# BatteryMonitor.net
KiCad netlist of a schematic drawn in Altium Designer
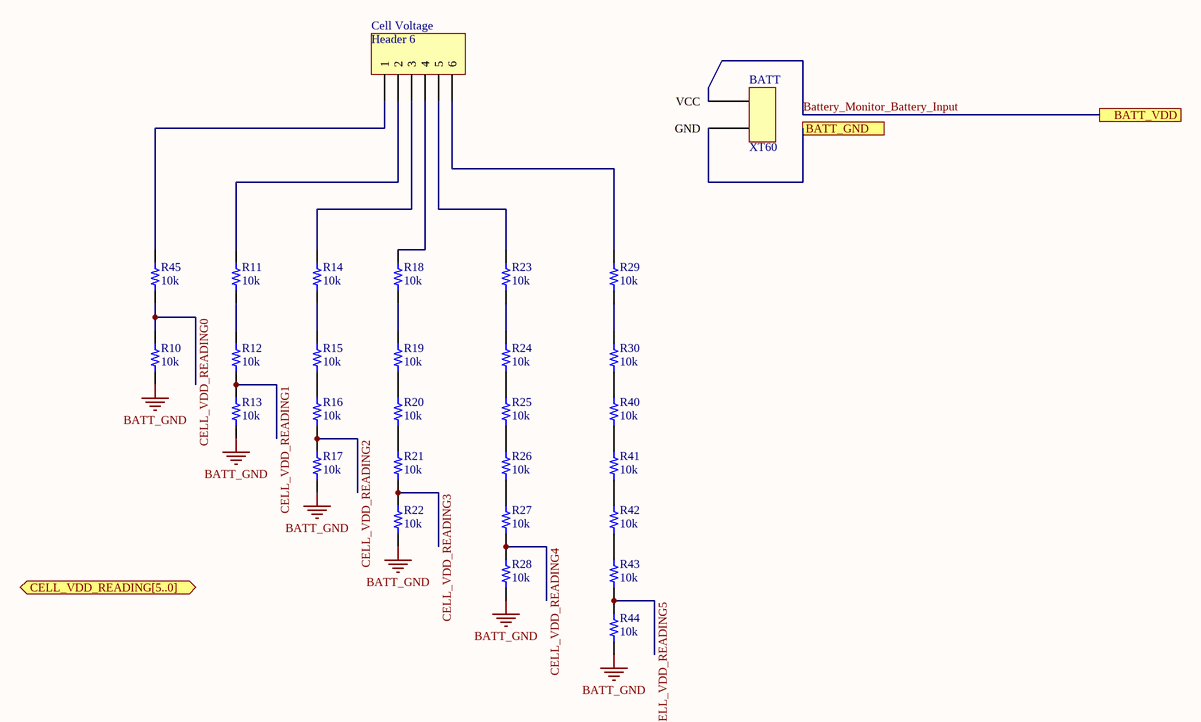
[diagram p0: BatteryMonitor.SchDoc]

(export (version "E")
  (design (tool "Eeschema 10.0.6"))
  (components
    (comp (ref "BATT") (value "XT60") (footprint "PcbLib2:XT60") (libsource (lib "Schlib2") (part "XT60")))
    (comp (ref "Cell Voltage")
      (value "Header 6")
      (footprint "HDR1X6")
      (description "Header, 6-Pin")
      (fields (field (name "PUBLISHER") "Altium Limited"))
      (libsource (lib "Miscellaneous Connectors") (part "Header 6"))
    )
    (comp (ref "R10")
      (value "10k")
      (footprint "RES 0402/1005")
      (description "RES SMD 10K OHM 1% 1/10W 0402")
      (fields
        (field (name "PART NUMBER") "ERJ-2RKF1002X")
        (field (name "MANUFACTURER") "Panasonic Electronic Components")
      )
      (libsource (lib "Celestial Library Database") (part "Resistor"))
    )
    (comp (ref "R11")
      (value "10k")
      (footprint "RES 0402/1005")
      (description "RES SMD 10K OHM 1% 1/10W 0402")
      (fields
        (field (name "PART NUMBER") "ERJ-2RKF1002X")
        (field (name "MANUFACTURER") "Panasonic Electronic Components")
      )
      (libsource (lib "Celestial Library Database") (part "Resistor"))
    )
    (comp (ref "R12")
      (value "10k")
      (footprint "RES 0402/1005")
      (description "RES SMD 10K OHM 1% 1/10W 0402")
      (fields
        (field (name "PART NUMBER") "ERJ-2RKF1002X")
        (field (name "MANUFACTURER") "Panasonic Electronic Components")
      )
      (libsource (lib "Celestial Library Database") (part "Resistor"))
    )
    (comp (ref "R13")
      (value "10k")
      (footprint "RES 0402/1005")
      (description "RES SMD 10K OHM 1% 1/10W 0402")
      (fields
        (field (name "PART NUMBER") "ERJ-2RKF1002X")
        (field (name "MANUFACTURER") "Panasonic Electronic Components")
      )
      (libsource (lib "Celestial Library Database") (part "Resistor"))
    )
    (comp (ref "R14")
      (value "10k")
      (footprint "RES 0402/1005")
      (description "RES SMD 10K OHM 1% 1/10W 0402")
      (fields
        (field (name "PART NUMBER") "ERJ-2RKF1002X")
        (field (name "MANUFACTURER") "Panasonic Electronic Components")
      )
      (libsource (lib "Celestial Library Database") (part "Resistor"))
    )
    (comp (ref "R15")
      (value "10k")
      (footprint "RES 0402/1005")
      (description "RES SMD 10K OHM 1% 1/10W 0402")
      (fields
        (field (name "PART NUMBER") "ERJ-2RKF1002X")
        (field (name "MANUFACTURER") "Panasonic Electronic Components")
      )
      (libsource (lib "Celestial Library Database") (part "Resistor"))
    )
    (comp (ref "R16")
      (value "10k")
      (footprint "RES 0402/1005")
      (description "RES SMD 10K OHM 1% 1/10W 0402")
      (fields
        (field (name "PART NUMBER") "ERJ-2RKF1002X")
        (field (name "MANUFACTURER") "Panasonic Electronic Components")
      )
      (libsource (lib "Celestial Library Database") (part "Resistor"))
    )
    (comp (ref "R17")
      (value "10k")
      (footprint "RES 0402/1005")
      (description "RES SMD 10K OHM 1% 1/10W 0402")
      (fields
        (field (name "PART NUMBER") "ERJ-2RKF1002X")
        (field (name "MANUFACTURER") "Panasonic Electronic Components")
      )
      (libsource (lib "Celestial Library Database") (part "Resistor"))
    )
    (comp (ref "R18")
      (value "10k")
      (footprint "RES 0402/1005")
      (description "RES SMD 10K OHM 1% 1/10W 0402")
      (fields
        (field (name "PART NUMBER") "ERJ-2RKF1002X")
        (field (name "MANUFACTURER") "Panasonic Electronic Components")
      )
      (libsource (lib "Celestial Library Database") (part "Resistor"))
    )
    (comp (ref "R19")
      (value "10k")
      (footprint "RES 0402/1005")
      (description "RES SMD 10K OHM 1% 1/10W 0402")
      (fields
        (field (name "PART NUMBER") "ERJ-2RKF1002X")
        (field (name "MANUFACTURER") "Panasonic Electronic Components")
      )
      (libsource (lib "Celestial Library Database") (part "Resistor"))
    )
    (comp (ref "R20")
      (value "10k")
      (footprint "RES 0402/1005")
      (description "RES SMD 10K OHM 1% 1/10W 0402")
      (fields
        (field (name "PART NUMBER") "ERJ-2RKF1002X")
        (field (name "MANUFACTURER") "Panasonic Electronic Components")
      )
      (libsource (lib "Celestial Library Database") (part "Resistor"))
    )
    (comp (ref "R21")
      (value "10k")
      (footprint "RES 0402/1005")
      (description "RES SMD 10K OHM 1% 1/10W 0402")
      (fields
        (field (name "PART NUMBER") "ERJ-2RKF1002X")
        (field (name "MANUFACTURER") "Panasonic Electronic Components")
      )
      (libsource (lib "Celestial Library Database") (part "Resistor"))
    )
    (comp (ref "R22")
      (value "10k")
      (footprint "RES 0402/1005")
      (description "RES SMD 10K OHM 1% 1/10W 0402")
      (fields
        (field (name "PART NUMBER") "ERJ-2RKF1002X")
        (field (name "MANUFACTURER") "Panasonic Electronic Components")
      )
      (libsource (lib "Celestial Library Database") (part "Resistor"))
    )
    (comp (ref "R23")
      (value "10k")
      (footprint "RES 0402/1005")
      (description "RES SMD 10K OHM 1% 1/10W 0402")
      (fields
        (field (name "PART NUMBER") "ERJ-2RKF1002X")
        (field (name "MANUFACTURER") "Panasonic Electronic Components")
      )
      (libsource (lib "Celestial Library Database") (part "Resistor"))
    )
    (comp (ref "R24")
      (value "10k")
      (footprint "RES 0402/1005")
      (description "RES SMD 10K OHM 1% 1/10W 0402")
      (fields
        (field (name "PART NUMBER") "ERJ-2RKF1002X")
        (field (name "MANUFACTURER") "Panasonic Electronic Components")
      )
      (libsource (lib "Celestial Library Database") (part "Resistor"))
    )
    (comp (ref "R25")
      (value "10k")
      (footprint "RES 0402/1005")
      (description "RES SMD 10K OHM 1% 1/10W 0402")
      (fields
        (field (name "PART NUMBER") "ERJ-2RKF1002X")
        (field (name "MANUFACTURER") "Panasonic Electronic Components")
      )
      (libsource (lib "Celestial Library Database") (part "Resistor"))
    )
    (comp (ref "R26")
      (value "10k")
      (footprint "RES 0402/1005")
      (description "RES SMD 10K OHM 1% 1/10W 0402")
      (fields
        (field (name "PART NUMBER") "ERJ-2RKF1002X")
        (field (name "MANUFACTURER") "Panasonic Electronic Components")
      )
      (libsource (lib "Celestial Library Database") (part "Resistor"))
    )
    (comp (ref "R27")
      (value "10k")
      (footprint "RES 0402/1005")
      (description "RES SMD 10K OHM 1% 1/10W 0402")
      (fields
        (field (name "PART NUMBER") "ERJ-2RKF1002X")
        (field (name "MANUFACTURER") "Panasonic Electronic Components")
      )
      (libsource (lib "Celestial Library Database") (part "Resistor"))
    )
    (comp (ref "R28")
      (value "10k")
      (footprint "RES 0402/1005")
      (description "RES SMD 10K OHM 1% 1/10W 0402")
      (fields
        (field (name "PART NUMBER") "ERJ-2RKF1002X")
        (field (name "MANUFACTURER") "Panasonic Electronic Components")
      )
      (libsource (lib "Celestial Library Database") (part "Resistor"))
    )
    (comp (ref "R29")
      (value "10k")
      (footprint "RES 0402/1005")
      (description "RES SMD 10K OHM 1% 1/10W 0402")
      (fields
        (field (name "PART NUMBER") "ERJ-2RKF1002X")
        (field (name "MANUFACTURER") "Panasonic Electronic Components")
      )
      (libsource (lib "Celestial Library Database") (part "Resistor"))
    )
    (comp (ref "R30")
      (value "10k")
      (footprint "RES 0402/1005")
      (description "RES SMD 10K OHM 1% 1/10W 0402")
      (fields
        (field (name "PART NUMBER") "ERJ-2RKF1002X")
        (field (name "MANUFACTURER") "Panasonic Electronic Components")
      )
      (libsource (lib "Celestial Library Database") (part "Resistor"))
    )
    (comp (ref "R40")
      (value "10k")
      (footprint "RES 0402/1005")
      (description "RES SMD 10K OHM 1% 1/10W 0402")
      (fields
        (field (name "PART NUMBER") "ERJ-2RKF1002X")
        (field (name "MANUFACTURER") "Panasonic Electronic Components")
      )
      (libsource (lib "Celestial Library Database") (part "Resistor"))
    )
    (comp (ref "R41")
      (value "10k")
      (footprint "RES 0402/1005")
      (description "RES SMD 10K OHM 1% 1/10W 0402")
      (fields
        (field (name "PART NUMBER") "ERJ-2RKF1002X")
        (field (name "MANUFACTURER") "Panasonic Electronic Components")
      )
      (libsource (lib "Celestial Library Database") (part "Resistor"))
    )
    (comp (ref "R42")
      (value "10k")
      (footprint "RES 0402/1005")
      (description "RES SMD 10K OHM 1% 1/10W 0402")
      (fields
        (field (name "PART NUMBER") "ERJ-2RKF1002X")
        (field (name "MANUFACTURER") "Panasonic Electronic Components")
      )
      (libsource (lib "Celestial Library Database") (part "Resistor"))
    )
    (comp (ref "R43")
      (value "10k")
      (footprint "RES 0402/1005")
      (description "RES SMD 10K OHM 1% 1/10W 0402")
      (fields
        (field (name "PART NUMBER") "ERJ-2RKF1002X")
        (field (name "MANUFACTURER") "Panasonic Electronic Components")
      )
      (libsource (lib "Celestial Library Database") (part "Resistor"))
    )
    (comp (ref "R44")
      (value "10k")
      (footprint "RES 0402/1005")
      (description "RES SMD 10K OHM 1% 1/10W 0402")
      (fields
        (field (name "PART NUMBER") "ERJ-2RKF1002X")
        (field (name "MANUFACTURER") "Panasonic Electronic Components")
      )
      (libsource (lib "Celestial Library Database") (part "Resistor"))
    )
    (comp (ref "R45")
      (value "10k")
      (footprint "RES 0402/1005")
      (description "RES SMD 10K OHM 1% 1/10W 0402")
      (fields
        (field (name "PART NUMBER") "ERJ-2RKF1002X")
        (field (name "MANUFACTURER") "Panasonic Electronic Components")
      )
      (libsource (lib "Celestial Library Database") (part "Resistor"))
    )
  )
  (nets
    (net (code "2") (name "/CELL_VDD_READING0") (class "Default")
      (node (ref "R10") (pin "2") (pinfunction "2_2") (pintype "passive"))
      (node (ref "R45") (pin "1") (pinfunction "1_1") (pintype "passive"))
    )
    (net (code "3") (name "/CELL_VDD_READING1") (class "Default")
      (node (ref "R12") (pin "1") (pinfunction "1_1") (pintype "passive"))
      (node (ref "R13") (pin "2") (pinfunction "2_2") (pintype "passive"))
    )
    (net (code "4") (name "/CELL_VDD_READING2") (class "Default")
      (node (ref "R16") (pin "1") (pinfunction "1_1") (pintype "passive"))
      (node (ref "R17") (pin "2") (pinfunction "2_2") (pintype "passive"))
    )
    (net (code "5") (name "/CELL_VDD_READING3") (class "Default")
      (node (ref "R21") (pin "1") (pinfunction "1_1") (pintype "passive"))
      (node (ref "R22") (pin "2") (pinfunction "2_2") (pintype "passive"))
    )
    (net (code "6") (name "/CELL_VDD_READING4") (class "Default")
      (node (ref "R27") (pin "1") (pinfunction "1_1") (pintype "passive"))
      (node (ref "R28") (pin "2") (pinfunction "2_2") (pintype "passive"))
    )
    (net (code "7") (name "/CELL_VDD_READING5") (class "Default")
      (node (ref "R43") (pin "1") (pinfunction "1_1") (pintype "passive"))
      (node (ref "R44") (pin "2") (pinfunction "2_2") (pintype "passive"))
    )
    (net (code "9") (name "BATT_GND") (class "Default")
      (node (ref "R10") (pin "1") (pinfunction "1_1") (pintype "passive"))
      (node (ref "R13") (pin "1") (pinfunction "1_1") (pintype "passive"))
      (node (ref "R17") (pin "1") (pinfunction "1_1") (pintype "passive"))
      (node (ref "R22") (pin "1") (pinfunction "1_1") (pintype "passive"))
      (node (ref "R28") (pin "1") (pinfunction "1_1") (pintype "passive"))
      (node (ref "R44") (pin "1") (pinfunction "1_1") (pintype "passive"))
    )
    (net (code "10") (name "Net-(Cell Voltage-Pad1)") (class "Default")
      (node (ref "Cell Voltage") (pin "1") (pinfunction "1_1") (pintype "passive"))
      (node (ref "R45") (pin "2") (pinfunction "2_2") (pintype "passive"))
    )
    (net (code "11") (name "Net-(Cell Voltage-Pad2)") (class "Default")
      (node (ref "Cell Voltage") (pin "2") (pinfunction "2_2") (pintype "passive"))
      (node (ref "R11") (pin "2") (pinfunction "2_2") (pintype "passive"))
    )
    (net (code "12") (name "Net-(Cell Voltage-Pad3)") (class "Default")
      (node (ref "Cell Voltage") (pin "3") (pinfunction "3_3") (pintype "passive"))
      (node (ref "R14") (pin "2") (pinfunction "2_2") (pintype "passive"))
    )
    (net (code "13") (name "Net-(Cell Voltage-Pad4)") (class "Default")
      (node (ref "Cell Voltage") (pin "4") (pinfunction "4_4") (pintype "passive"))
      (node (ref "R18") (pin "2") (pinfunction "2_2") (pintype "passive"))
    )
    (net (code "14") (name "Net-(Cell Voltage-Pad5)") (class "Default")
      (node (ref "Cell Voltage") (pin "5") (pinfunction "5_5") (pintype "passive"))
      (node (ref "R23") (pin "2") (pinfunction "2_2") (pintype "passive"))
    )
    (net (code "15") (name "Net-(Cell Voltage-Pad6)") (class "Default")
      (node (ref "Cell Voltage") (pin "6") (pinfunction "6_6") (pintype "passive"))
      (node (ref "R29") (pin "2") (pinfunction "2_2") (pintype "passive"))
    )
    (net (code "16") (name "Net-(R11-Pad1)") (class "Default")
      (node (ref "R11") (pin "1") (pinfunction "1_1") (pintype "passive"))
      (node (ref "R12") (pin "2") (pinfunction "2_2") (pintype "passive"))
    )
    (net (code "17") (name "Net-(R14-Pad1)") (class "Default")
      (node (ref "R14") (pin "1") (pinfunction "1_1") (pintype "passive"))
      (node (ref "R15") (pin "2") (pinfunction "2_2") (pintype "passive"))
    )
    (net (code "18") (name "Net-(R15-Pad1)") (class "Default")
      (node (ref "R15") (pin "1") (pinfunction "1_1") (pintype "passive"))
      (node (ref "R16") (pin "2") (pinfunction "2_2") (pintype "passive"))
    )
    (net (code "19") (name "Net-(R18-Pad1)") (class "Default")
      (node (ref "R18") (pin "1") (pinfunction "1_1") (pintype "passive"))
      (node (ref "R19") (pin "2") (pinfunction "2_2") (pintype "passive"))
    )
    (net (code "20") (name "Net-(R19-Pad1)") (class "Default")
      (node (ref "R19") (pin "1") (pinfunction "1_1") (pintype "passive"))
      (node (ref "R20") (pin "2") (pinfunction "2_2") (pintype "passive"))
    )
    (net (code "21") (name "Net-(R20-Pad1)") (class "Default")
      (node (ref "R20") (pin "1") (pinfunction "1_1") (pintype "passive"))
      (node (ref "R21") (pin "2") (pinfunction "2_2") (pintype "passive"))
    )
    (net (code "22") (name "Net-(R23-Pad1)") (class "Default")
      (node (ref "R23") (pin "1") (pinfunction "1_1") (pintype "passive"))
      (node (ref "R24") (pin "2") (pinfunction "2_2") (pintype "passive"))
    )
    (net (code "23") (name "Net-(R24-Pad1)") (class "Default")
      (node (ref "R24") (pin "1") (pinfunction "1_1") (pintype "passive"))
      (node (ref "R25") (pin "2") (pinfunction "2_2") (pintype "passive"))
    )
    (net (code "24") (name "Net-(R25-Pad1)") (class "Default")
      (node (ref "R25") (pin "1") (pinfunction "1_1") (pintype "passive"))
      (node (ref "R26") (pin "2") (pinfunction "2_2") (pintype "passive"))
    )
    (net (code "25") (name "Net-(R26-Pad1)") (class "Default")
      (node (ref "R26") (pin "1") (pinfunction "1_1") (pintype "passive"))
      (node (ref "R27") (pin "2") (pinfunction "2_2") (pintype "passive"))
    )
    (net (code "26") (name "Net-(R29-Pad1)") (class "Default")
      (node (ref "R29") (pin "1") (pinfunction "1_1") (pintype "passive"))
      (node (ref "R30") (pin "2") (pinfunction "2_2") (pintype "passive"))
    )
    (net (code "27") (name "Net-(R30-Pad1)") (class "Default")
      (node (ref "R30") (pin "1") (pinfunction "1_1") (pintype "passive"))
      (node (ref "R40") (pin "2") (pinfunction "2_2") (pintype "passive"))
    )
    (net (code "28") (name "Net-(R40-Pad1)") (class "Default")
      (node (ref "R40") (pin "1") (pinfunction "1_1") (pintype "passive"))
      (node (ref "R41") (pin "2") (pinfunction "2_2") (pintype "passive"))
    )
    (net (code "29") (name "Net-(R41-Pad1)") (class "Default")
      (node (ref "R41") (pin "1") (pinfunction "1_1") (pintype "passive"))
      (node (ref "R42") (pin "2") (pinfunction "2_2") (pintype "passive"))
    )
    (net (code "30") (name "Net-(R42-Pad1)") (class "Default")
      (node (ref "R42") (pin "1") (pinfunction "1_1") (pintype "passive"))
      (node (ref "R43") (pin "2") (pinfunction "2_2") (pintype "passive"))
    )
    (net (code "31") (name "unconnected-(BATT-PadGND)") (class "Default")
      (node (ref "BATT") (pin "GND") (pinfunction "GND_GND") (pintype "power_in"))
    )
    (net (code "32") (name "unconnected-(BATT-PadVCC)") (class "Default")
      (node (ref "BATT") (pin "VCC") (pinfunction "VCC_VCC") (pintype "power_in"))
    )
  )
)
